# H-Bridge_v2.net
KiCad netlist of a schematic drawn in EAGLE
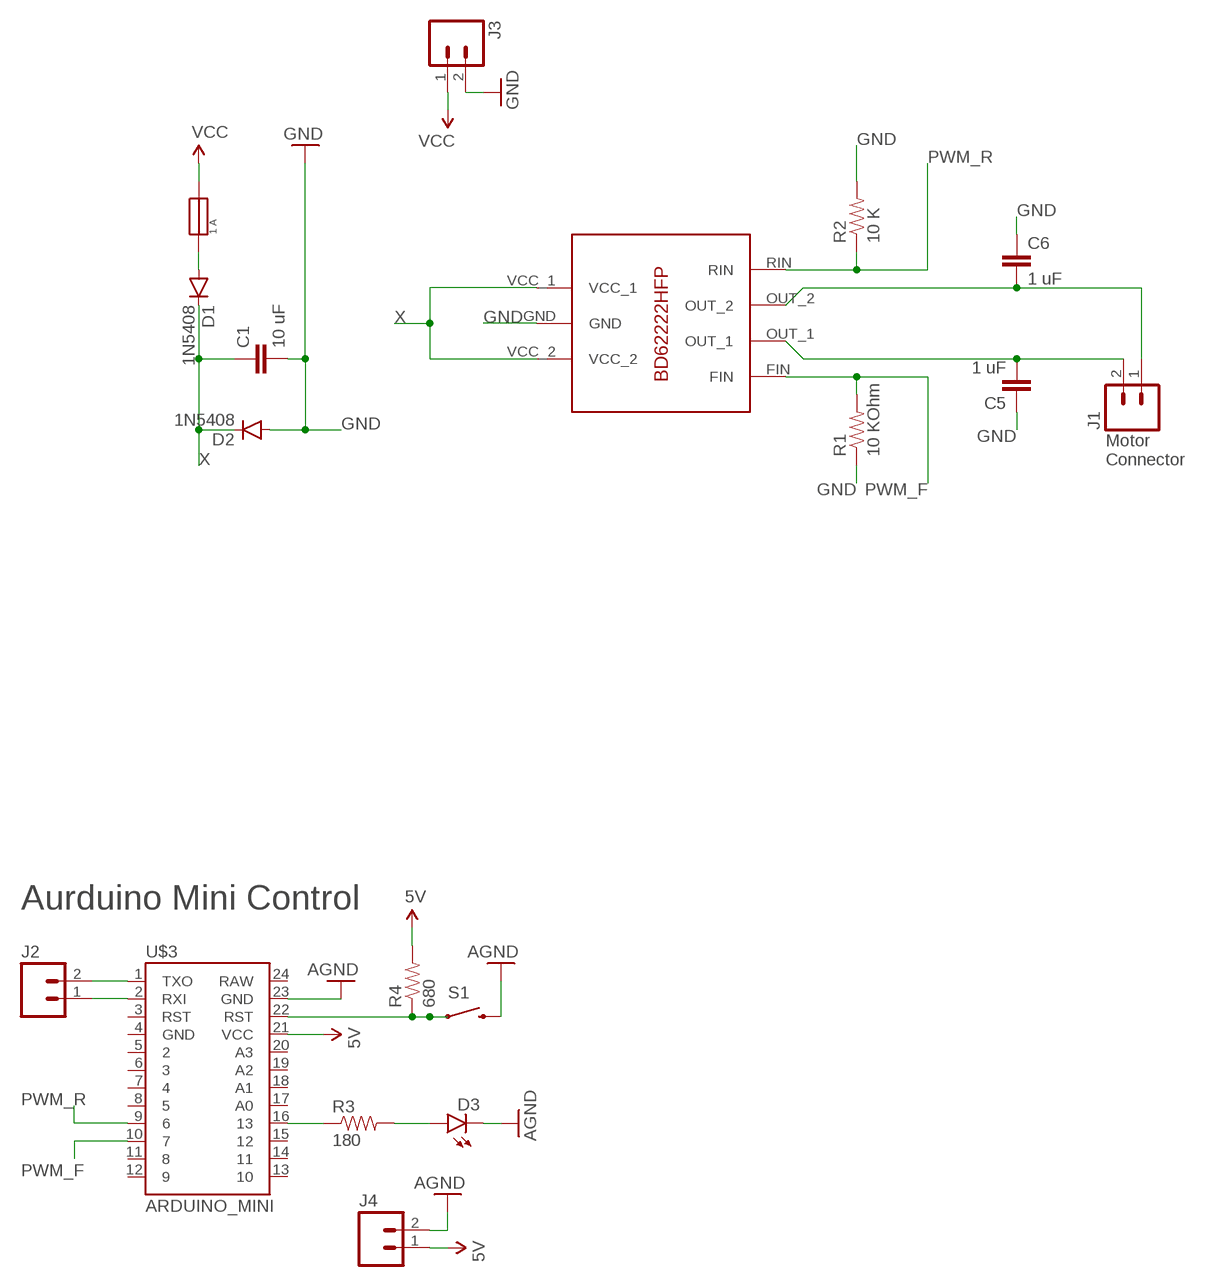
[diagram p0: schematic, sheet 1]

(export (version "E")
  (design (tool "Eeschema 10.0.6"))
  (components
    (comp (ref "C1")
      (value "10 uF")
      (footprint "eagle-import:0805")
      (libsource (lib "eagle-import") (part "CAP0805"))
    )
    (comp (ref "C5")
      (value "1 uF")
      (footprint "eagle-import:0805")
      (libsource (lib "eagle-import") (part "CAP0805"))
    )
    (comp (ref "C6")
      (value "1 uF")
      (footprint "eagle-import:0805")
      (libsource (lib "eagle-import") (part "CAP0805"))
    )
    (comp (ref "D1")
      (value "1N5408")
      (footprint "eagle-import:DIODE-1N4148")
      (libsource (lib "eagle-import") (part "DIODE1N4148"))
    )
    (comp (ref "D2")
      (value "1N5408")
      (footprint "eagle-import:DIODE-1N4148")
      (libsource (lib "eagle-import") (part "DIODE1N4148"))
    )
    (comp (ref "D3")
      (value "LED3MM")
      (footprint "eagle-import:LED3MM")
      (libsource (lib "eagle-import") (part "LED3MM"))
    )
    (comp (ref "J1")
      (value "M023.5MM")
      (footprint "eagle-import:SCREWTERMINAL-3.5MM-2")
      (libsource (lib "eagle-import") (part "M023.5MM"))
    )
    (comp (ref "J2")
      (value "M02LOCK")
      (footprint "eagle-import:1X02_LOCK")
      (libsource (lib "eagle-import") (part "M02LOCK"))
    )
    (comp (ref "J3")
      (value "M023.5MM")
      (footprint "eagle-import:SCREWTERMINAL-3.5MM-2")
      (libsource (lib "eagle-import") (part "M023.5MM"))
    )
    (comp (ref "J4")
      (value "M023.5MM")
      (footprint "eagle-import:SCREWTERMINAL-3.5MM-2")
      (libsource (lib "eagle-import") (part "M023.5MM"))
    )
    (comp (ref "R1")
      (value "10 KOhm")
      (footprint "eagle-import:1_6W-RES")
      (libsource (lib "eagle-import") (part "RESISTORPTH-1/6W"))
    )
    (comp (ref "R2")
      (value "10 K")
      (footprint "eagle-import:1_6W-RES")
      (libsource (lib "eagle-import") (part "RESISTORPTH-1/6W"))
    )
    (comp (ref "R3")
      (value "180")
      (footprint "eagle-import:AXIAL-0.3")
      (libsource (lib "eagle-import") (part "RESISTORAXIAL-0.3"))
    )
    (comp (ref "R4")
      (value "680")
      (footprint "eagle-import:AXIAL-0.3")
      (libsource (lib "eagle-import") (part "RESISTORAXIAL-0.3"))
    )
    (comp (ref "S1")
      (value "SWITCH-MOMENTARY-2PTH")
      (footprint "eagle-import:TACTILE-PTH")
      (libsource (lib "eagle-import") (part "SWITCH-MOMENTARY-2PTH"))
    )
    (comp (ref "U$1")
      (value "BD62222HFP")
      (footprint "eagle-import:BD62222HFP")
      (libsource (lib "eagle-import") (part "BD62222HFP"))
    )
    (comp (ref "U$3")
      (value "ARDUINO_MINI")
      (footprint "eagle-import:ARDUINO_MINI")
      (libsource (lib "eagle-import") (part "ARDUINO_MINI"))
    )
    (comp (ref "U$8")
      (value "1 A")
      (footprint "eagle-import:5MM_PC_FUSE_HOLDER_KEYSTONE_ELEC")
      (libsource (lib "eagle-import") (part "5MM_PC_FUSE_HOLDER_KEYSTONE_ELEC"))
    )
  )
  (nets
    (net (code "1") (name "/PWM_F") (class "Default")
      (node (ref "R1") (pin "2") (pinfunction "2_2") (pintype "passive"))
      (node (ref "U$1") (pin "FIN") (pinfunction "FIN_FIN") (pintype "bidirectional"))
      (node (ref "U$3") (pin "10") (pinfunction "7_10") (pintype "bidirectional"))
    )
    (net (code "2") (name "/PWM_R") (class "Default")
      (node (ref "R2") (pin "1") (pinfunction "1_1") (pintype "passive"))
      (node (ref "U$1") (pin "RIN") (pinfunction "RIN_RIN") (pintype "bidirectional"))
      (node (ref "U$3") (pin "9") (pinfunction "6_9") (pintype "bidirectional"))
    )
    (net (code "3") (name "/X") (class "Default")
      (node (ref "C1") (pin "1") (pinfunction "1_1") (pintype "passive"))
      (node (ref "D1") (pin "C") (pinfunction "C_C") (pintype "passive"))
      (node (ref "D2") (pin "C") (pinfunction "C_C") (pintype "passive"))
      (node (ref "U$1") (pin "VCC_1") (pinfunction "VCC_1_VCC_1") (pintype "bidirectional"))
      (node (ref "U$1") (pin "VCC_2") (pinfunction "VCC_2_VCC_2") (pintype "bidirectional"))
    )
    (net (code "4") (name "5V") (class "Default")
      (node (ref "J4") (pin "1") (pinfunction "1_1") (pintype "passive"))
      (node (ref "R4") (pin "P$2") (pinfunction "2_P$2") (pintype "passive"))
      (node (ref "U$3") (pin "21") (pinfunction "VCC_21") (pintype "bidirectional"))
    )
    (net (code "5") (name "AGND") (class "Default")
      (node (ref "D3") (pin "K") (pinfunction "C_K") (pintype "passive"))
      (node (ref "J4") (pin "2") (pinfunction "2_2") (pintype "passive"))
      (node (ref "S1") (pin "3") (pinfunction "2_3") (pintype "passive"))
      (node (ref "U$3") (pin "23") (pinfunction "GND_23") (pintype "bidirectional"))
    )
    (net (code "6") (name "GND") (class "Default")
      (node (ref "C1") (pin "2") (pinfunction "2_2") (pintype "passive"))
      (node (ref "C5") (pin "1") (pinfunction "1_1") (pintype "passive"))
      (node (ref "C6") (pin "1") (pinfunction "1_1") (pintype "passive"))
      (node (ref "D2") (pin "A") (pinfunction "A_A") (pintype "passive"))
      (node (ref "J3") (pin "2") (pinfunction "2_2") (pintype "passive"))
      (node (ref "R1") (pin "1") (pinfunction "1_1") (pintype "passive"))
      (node (ref "R2") (pin "2") (pinfunction "2_2") (pintype "passive"))
      (node (ref "U$1") (pin "GND") (pinfunction "GND_GND") (pintype "bidirectional"))
    )
    (net (code "7") (name "Net-(C5-Pad2)") (class "Default")
      (node (ref "C5") (pin "2") (pinfunction "2_2") (pintype "passive"))
      (node (ref "J1") (pin "2") (pinfunction "2_2") (pintype "passive"))
      (node (ref "U$1") (pin "OUT_1") (pinfunction "OUT_1_OUT_1") (pintype "bidirectional"))
    )
    (net (code "8") (name "Net-(C6-Pad2)") (class "Default")
      (node (ref "C6") (pin "2") (pinfunction "2_2") (pintype "passive"))
      (node (ref "J1") (pin "1") (pinfunction "1_1") (pintype "passive"))
      (node (ref "U$1") (pin "OUT_2") (pinfunction "OUT_2_OUT_2") (pintype "bidirectional"))
    )
    (net (code "9") (name "Net-(D1-PadA)") (class "Default")
      (node (ref "D1") (pin "A") (pinfunction "A_A") (pintype "passive"))
      (node (ref "U$8") (pin "P$2") (pinfunction "P$2_P$2") (pintype "bidirectional"))
    )
    (net (code "10") (name "Net-(R3-1)") (class "Default")
      (node (ref "R3") (pin "P$1") (pinfunction "1_P$1") (pintype "passive"))
      (node (ref "U$3") (pin "16") (pinfunction "13_16") (pintype "bidirectional"))
    )
    (net (code "11") (name "Net-(R3-2)") (class "Default")
      (node (ref "D3") (pin "A") (pinfunction "A_A") (pintype "passive"))
      (node (ref "R3") (pin "P$2") (pinfunction "2_P$2") (pintype "passive"))
    )
    (net (code "12") (name "Net-(R4-1)") (class "Default")
      (node (ref "R4") (pin "P$1") (pinfunction "1_P$1") (pintype "passive"))
      (node (ref "S1") (pin "1") (pinfunction "1_1") (pintype "passive"))
      (node (ref "U$3") (pin "22") (pinfunction "RST_22") (pintype "bidirectional"))
    )
    (net (code "13") (name "Net-(U$3-RXI)") (class "Default")
      (node (ref "J2") (pin "1") (pinfunction "1_1") (pintype "passive"))
      (node (ref "U$3") (pin "2") (pinfunction "RXI_2") (pintype "bidirectional"))
    )
    (net (code "14") (name "Net-(U$3-TXO)") (class "Default")
      (node (ref "J2") (pin "2") (pinfunction "2_2") (pintype "passive"))
      (node (ref "U$3") (pin "1") (pinfunction "TXO_1") (pintype "bidirectional"))
    )
    (net (code "15") (name "VCC") (class "Default")
      (node (ref "J3") (pin "1") (pinfunction "1_1") (pintype "passive"))
      (node (ref "U$8") (pin "P$1") (pinfunction "P$1_P$1") (pintype "bidirectional"))
    )
    (net (code "16") (name "unconnected-(U$3-2-Pad5)") (class "Default")
      (node (ref "U$3") (pin "5") (pinfunction "2_5") (pintype "bidirectional"))
    )
    (net (code "17") (name "unconnected-(U$3-3-Pad6)") (class "Default")
      (node (ref "U$3") (pin "6") (pinfunction "3_6") (pintype "bidirectional"))
    )
    (net (code "18") (name "unconnected-(U$3-4-Pad7)") (class "Default")
      (node (ref "U$3") (pin "7") (pinfunction "4_7") (pintype "bidirectional"))
    )
    (net (code "19") (name "unconnected-(U$3-5-Pad8)") (class "Default")
      (node (ref "U$3") (pin "8") (pinfunction "5_8") (pintype "bidirectional"))
    )
    (net (code "20") (name "unconnected-(U$3-8-Pad11)") (class "Default")
      (node (ref "U$3") (pin "11") (pinfunction "8_11") (pintype "bidirectional"))
    )
    (net (code "21") (name "unconnected-(U$3-9-Pad12)") (class "Default")
      (node (ref "U$3") (pin "12") (pinfunction "9_12") (pintype "bidirectional"))
    )
    (net (code "22") (name "unconnected-(U$3-10-Pad13)") (class "Default")
      (node (ref "U$3") (pin "13") (pinfunction "10_13") (pintype "bidirectional"))
    )
    (net (code "23") (name "unconnected-(U$3-11-Pad14)") (class "Default")
      (node (ref "U$3") (pin "14") (pinfunction "11_14") (pintype "bidirectional"))
    )
    (net (code "24") (name "unconnected-(U$3-12-Pad15)") (class "Default")
      (node (ref "U$3") (pin "15") (pinfunction "12_15") (pintype "bidirectional"))
    )
    (net (code "25") (name "unconnected-(U$3-A0-Pad17)") (class "Default")
      (node (ref "U$3") (pin "17") (pinfunction "A0_17") (pintype "bidirectional"))
    )
    (net (code "26") (name "unconnected-(U$3-A1-Pad18)") (class "Default")
      (node (ref "U$3") (pin "18") (pinfunction "A1_18") (pintype "bidirectional"))
    )
    (net (code "27") (name "unconnected-(U$3-A2-Pad19)") (class "Default")
      (node (ref "U$3") (pin "19") (pinfunction "A2_19") (pintype "bidirectional"))
    )
    (net (code "28") (name "unconnected-(U$3-A3-Pad20)") (class "Default")
      (node (ref "U$3") (pin "20") (pinfunction "A3_20") (pintype "bidirectional"))
    )
    (net (code "29") (name "unconnected-(U$3-GND-Pad4)") (class "Default")
      (node (ref "U$3") (pin "4") (pinfunction "GND_4") (pintype "bidirectional"))
    )
    (net (code "30") (name "unconnected-(U$3-RAW-Pad24)") (class "Default")
      (node (ref "U$3") (pin "24") (pinfunction "RAW_24") (pintype "bidirectional"))
    )
    (net (code "31") (name "unconnected-(U$3-RST-Pad3)") (class "Default")
      (node (ref "U$3") (pin "3") (pinfunction "RST_3") (pintype "bidirectional"))
    )
  )
)
